# 06_LMS7002M_Power.net
KiCad netlist of a schematic drawn in Altium Designer
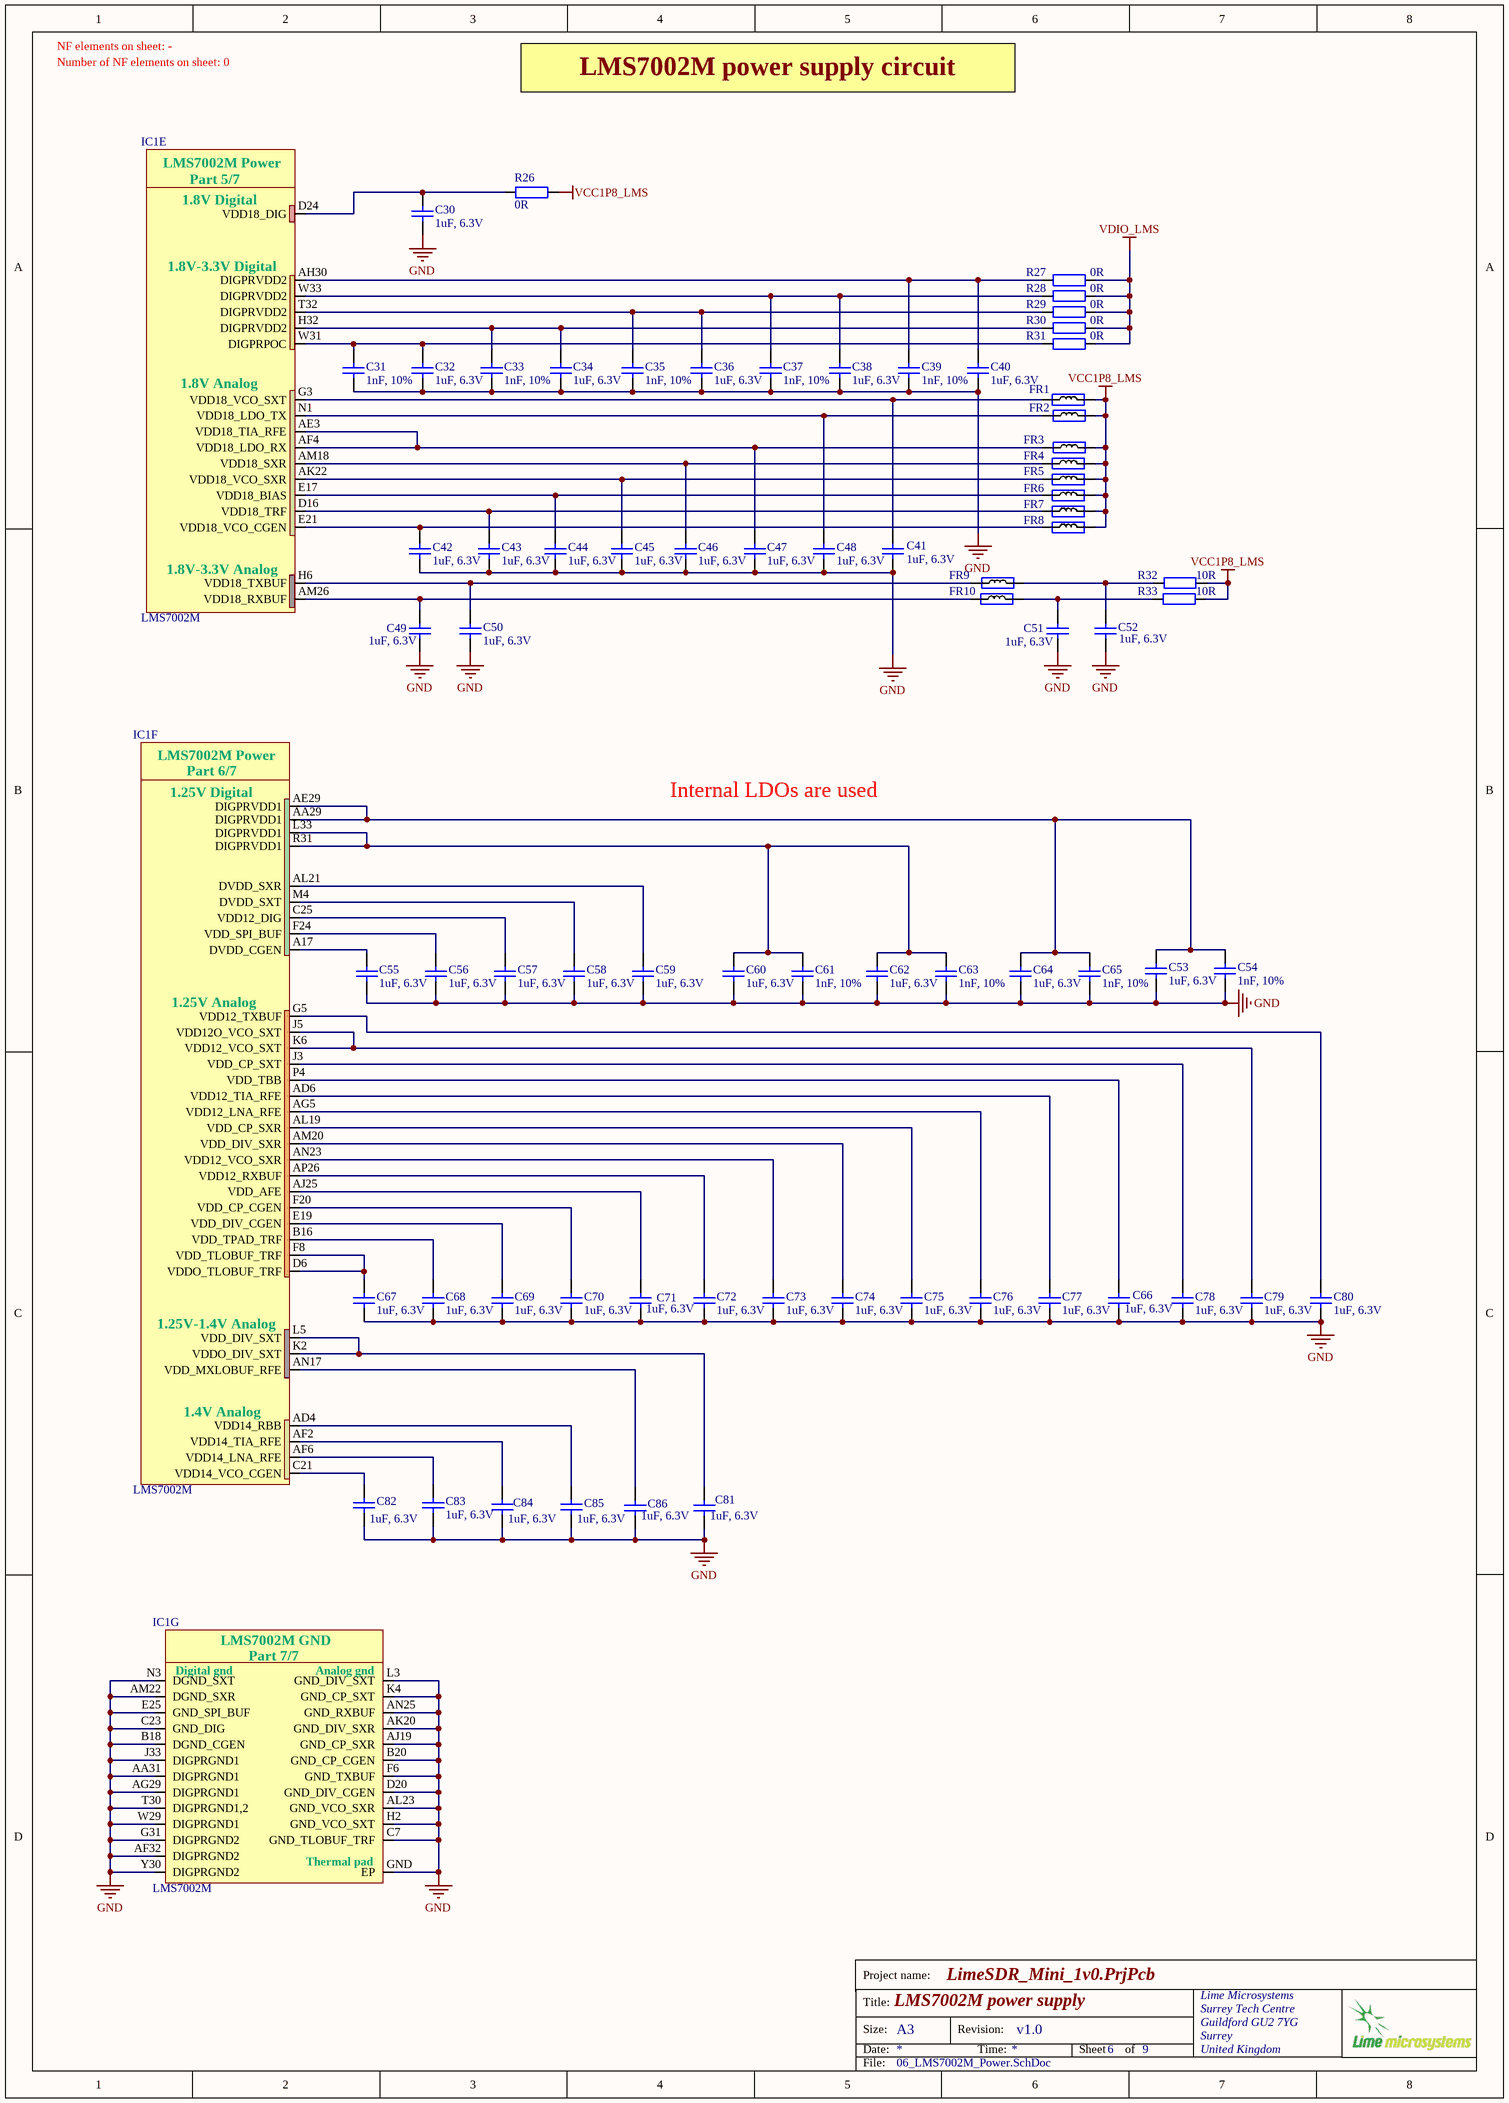
[diagram p0: 06_LMS7002M_Power.SchDoc]

(export (version "E")
  (design (tool "Eeschema 10.0.6"))
  (components
    (comp (ref "C30")
      (value "1uF, 6.3V")
      (footprint "CAP0201")
      (fields (field (name "TOLERANCE") "±20%") (field (name "MANUFACTURER") "TDK Corporation"))
      (libsource (lib "LimeMicroAltiumLib_schLib") (part "Cap_0402"))
    )
    (comp (ref "C31")
      (value "1nF, 10%")
      (footprint "CAP0201")
      (fields (field (name "TOLERANCE") "±10%") (field (name "MANUFACTURER") "TDK Corporation"))
      (libsource (lib "LimeMicroAltiumLib_schLib") (part "Cap_0402"))
    )
    (comp (ref "C32")
      (value "1uF, 6.3V")
      (footprint "CAP0201")
      (fields (field (name "TOLERANCE") "±20%") (field (name "MANUFACTURER") "TDK Corporation"))
      (libsource (lib "LimeMicroAltiumLib_schLib") (part "Cap_0402"))
    )
    (comp (ref "C33")
      (value "1nF, 10%")
      (footprint "CAP0201")
      (fields (field (name "TOLERANCE") "±10%") (field (name "MANUFACTURER") "TDK Corporation"))
      (libsource (lib "LimeMicroAltiumLib_schLib") (part "Cap_0402"))
    )
    (comp (ref "C34")
      (value "1uF, 6.3V")
      (footprint "CAP0201")
      (fields (field (name "TOLERANCE") "±20%") (field (name "MANUFACTURER") "TDK Corporation"))
      (libsource (lib "LimeMicroAltiumLib_schLib") (part "Cap_0402"))
    )
    (comp (ref "C35")
      (value "1nF, 10%")
      (footprint "CAP0201")
      (fields (field (name "TOLERANCE") "±10%") (field (name "MANUFACTURER") "TDK Corporation"))
      (libsource (lib "LimeMicroAltiumLib_schLib") (part "Cap_0402"))
    )
    (comp (ref "C36")
      (value "1uF, 6.3V")
      (footprint "CAP0201")
      (fields (field (name "TOLERANCE") "±20%") (field (name "MANUFACTURER") "TDK Corporation"))
      (libsource (lib "LimeMicroAltiumLib_schLib") (part "Cap_0402"))
    )
    (comp (ref "C37")
      (value "1nF, 10%")
      (footprint "CAP0201")
      (fields (field (name "TOLERANCE") "±10%") (field (name "MANUFACTURER") "TDK Corporation"))
      (libsource (lib "LimeMicroAltiumLib_schLib") (part "Cap_0402"))
    )
    (comp (ref "C38")
      (value "1uF, 6.3V")
      (footprint "CAP0201")
      (fields (field (name "TOLERANCE") "±20%") (field (name "MANUFACTURER") "TDK Corporation"))
      (libsource (lib "LimeMicroAltiumLib_schLib") (part "Cap_0402"))
    )
    (comp (ref "C39")
      (value "1nF, 10%")
      (footprint "CAP0201")
      (fields (field (name "TOLERANCE") "±10%") (field (name "MANUFACTURER") "TDK Corporation"))
      (libsource (lib "LimeMicroAltiumLib_schLib") (part "Cap_0402"))
    )
    (comp (ref "C40")
      (value "1uF, 6.3V")
      (footprint "CAP0201")
      (fields (field (name "TOLERANCE") "±20%") (field (name "MANUFACTURER") "TDK Corporation"))
      (libsource (lib "LimeMicroAltiumLib_schLib") (part "Cap_0402"))
    )
    (comp (ref "C41")
      (value "1uF, 6.3V")
      (footprint "CAP0201")
      (fields (field (name "TOLERANCE") "±20%") (field (name "MANUFACTURER") "TDK Corporation"))
      (libsource (lib "LimeMicroAltiumLib_schLib") (part "Cap_0402"))
    )
    (comp (ref "C42")
      (value "1uF, 6.3V")
      (footprint "CAP0201")
      (fields (field (name "TOLERANCE") "±20%") (field (name "MANUFACTURER") "TDK Corporation"))
      (libsource (lib "LimeMicroAltiumLib_schLib") (part "Cap_0402"))
    )
    (comp (ref "C43")
      (value "1uF, 6.3V")
      (footprint "CAP0201")
      (fields (field (name "TOLERANCE") "±20%") (field (name "MANUFACTURER") "TDK Corporation"))
      (libsource (lib "LimeMicroAltiumLib_schLib") (part "Cap_0402"))
    )
    (comp (ref "C44")
      (value "1uF, 6.3V")
      (footprint "CAP0201")
      (fields (field (name "TOLERANCE") "±20%") (field (name "MANUFACTURER") "TDK Corporation"))
      (libsource (lib "LimeMicroAltiumLib_schLib") (part "Cap_0402"))
    )
    (comp (ref "C45")
      (value "1uF, 6.3V")
      (footprint "CAP0201")
      (fields (field (name "TOLERANCE") "±20%") (field (name "MANUFACTURER") "TDK Corporation"))
      (libsource (lib "LimeMicroAltiumLib_schLib") (part "Cap_0402"))
    )
    (comp (ref "C46")
      (value "1uF, 6.3V")
      (footprint "CAP0201")
      (fields (field (name "TOLERANCE") "±20%") (field (name "MANUFACTURER") "TDK Corporation"))
      (libsource (lib "LimeMicroAltiumLib_schLib") (part "Cap_0402"))
    )
    (comp (ref "C47")
      (value "1uF, 6.3V")
      (footprint "CAP0201")
      (fields (field (name "TOLERANCE") "±20%") (field (name "MANUFACTURER") "TDK Corporation"))
      (libsource (lib "LimeMicroAltiumLib_schLib") (part "Cap_0402"))
    )
    (comp (ref "C48")
      (value "1uF, 6.3V")
      (footprint "CAP0201")
      (fields (field (name "TOLERANCE") "±20%") (field (name "MANUFACTURER") "TDK Corporation"))
      (libsource (lib "LimeMicroAltiumLib_schLib") (part "Cap_0402"))
    )
    (comp (ref "C49")
      (value "1uF, 6.3V")
      (footprint "CAP0201")
      (fields (field (name "TOLERANCE") "±20%") (field (name "MANUFACTURER") "TDK Corporation"))
      (libsource (lib "LimeMicroAltiumLib_schLib") (part "Cap_0402"))
    )
    (comp (ref "C50")
      (value "1uF, 6.3V")
      (footprint "CAP0201")
      (fields (field (name "TOLERANCE") "±20%") (field (name "MANUFACTURER") "TDK Corporation"))
      (libsource (lib "LimeMicroAltiumLib_schLib") (part "Cap_0402"))
    )
    (comp (ref "C51")
      (value "1uF, 6.3V")
      (footprint "CAP0201")
      (fields (field (name "TOLERANCE") "±20%") (field (name "MANUFACTURER") "TDK Corporation"))
      (libsource (lib "LimeMicroAltiumLib_schLib") (part "Cap_0402"))
    )
    (comp (ref "C52")
      (value "1uF, 6.3V")
      (footprint "CAP0201")
      (fields (field (name "TOLERANCE") "±20%") (field (name "MANUFACTURER") "TDK Corporation"))
      (libsource (lib "LimeMicroAltiumLib_schLib") (part "Cap_0402"))
    )
    (comp (ref "C53")
      (value "1uF, 6.3V")
      (footprint "CAP0201")
      (fields (field (name "TOLERANCE") "±20%") (field (name "MANUFACTURER") "TDK Corporation"))
      (libsource (lib "LimeMicroAltiumLib_schLib") (part "Cap_0402"))
    )
    (comp (ref "C54")
      (value "1nF, 10%")
      (footprint "CAP0201")
      (fields (field (name "TOLERANCE") "±10%") (field (name "MANUFACTURER") "TDK Corporation"))
      (libsource (lib "LimeMicroAltiumLib_schLib") (part "Cap_0402"))
    )
    (comp (ref "C55")
      (value "1uF, 6.3V")
      (footprint "CAP0201")
      (fields (field (name "TOLERANCE") "±20%") (field (name "MANUFACTURER") "TDK Corporation"))
      (libsource (lib "LimeMicroAltiumLib_schLib") (part "Cap_0402"))
    )
    (comp (ref "C56")
      (value "1uF, 6.3V")
      (footprint "CAP0201")
      (fields (field (name "TOLERANCE") "±20%") (field (name "MANUFACTURER") "TDK Corporation"))
      (libsource (lib "LimeMicroAltiumLib_schLib") (part "Cap_0402"))
    )
    (comp (ref "C57")
      (value "1uF, 6.3V")
      (footprint "CAP0201")
      (fields (field (name "TOLERANCE") "±20%") (field (name "MANUFACTURER") "TDK Corporation"))
      (libsource (lib "LimeMicroAltiumLib_schLib") (part "Cap_0402"))
    )
    (comp (ref "C58")
      (value "1uF, 6.3V")
      (footprint "CAP0201")
      (fields (field (name "TOLERANCE") "±20%") (field (name "MANUFACTURER") "TDK Corporation"))
      (libsource (lib "LimeMicroAltiumLib_schLib") (part "Cap_0402"))
    )
    (comp (ref "C59")
      (value "1uF, 6.3V")
      (footprint "CAP0201")
      (fields (field (name "TOLERANCE") "±20%") (field (name "MANUFACTURER") "TDK Corporation"))
      (libsource (lib "LimeMicroAltiumLib_schLib") (part "Cap_0402"))
    )
    (comp (ref "C60")
      (value "1uF, 6.3V")
      (footprint "CAP0201")
      (fields (field (name "TOLERANCE") "±20%") (field (name "MANUFACTURER") "TDK Corporation"))
      (libsource (lib "LimeMicroAltiumLib_schLib") (part "Cap_0402"))
    )
    (comp (ref "C61")
      (value "1nF, 10%")
      (footprint "CAP0201")
      (fields (field (name "TOLERANCE") "±10%") (field (name "MANUFACTURER") "TDK Corporation"))
      (libsource (lib "LimeMicroAltiumLib_schLib") (part "Cap_0402"))
    )
    (comp (ref "C62")
      (value "1uF, 6.3V")
      (footprint "CAP0201")
      (fields (field (name "TOLERANCE") "±20%") (field (name "MANUFACTURER") "TDK Corporation"))
      (libsource (lib "LimeMicroAltiumLib_schLib") (part "Cap_0402"))
    )
    (comp (ref "C63")
      (value "1nF, 10%")
      (footprint "CAP0201")
      (fields (field (name "TOLERANCE") "±10%") (field (name "MANUFACTURER") "TDK Corporation"))
      (libsource (lib "LimeMicroAltiumLib_schLib") (part "Cap_0402"))
    )
    (comp (ref "C64")
      (value "1uF, 6.3V")
      (footprint "CAP0201")
      (fields (field (name "TOLERANCE") "±20%") (field (name "MANUFACTURER") "TDK Corporation"))
      (libsource (lib "LimeMicroAltiumLib_schLib") (part "Cap_0402"))
    )
    (comp (ref "C65")
      (value "1nF, 10%")
      (footprint "CAP0201")
      (fields (field (name "TOLERANCE") "±10%") (field (name "MANUFACTURER") "TDK Corporation"))
      (libsource (lib "LimeMicroAltiumLib_schLib") (part "Cap_0402"))
    )
    (comp (ref "C66")
      (value "1uF, 6.3V")
      (footprint "CAP0201")
      (fields (field (name "TOLERANCE") "±20%") (field (name "MANUFACTURER") "TDK Corporation"))
      (libsource (lib "LimeMicroAltiumLib_schLib") (part "Cap_0402"))
    )
    (comp (ref "C67")
      (value "1uF, 6.3V")
      (footprint "CAP0201")
      (fields (field (name "TOLERANCE") "±20%") (field (name "MANUFACTURER") "TDK Corporation"))
      (libsource (lib "LimeMicroAltiumLib_schLib") (part "Cap_0402"))
    )
    (comp (ref "C68")
      (value "1uF, 6.3V")
      (footprint "CAP0201")
      (fields (field (name "TOLERANCE") "±20%") (field (name "MANUFACTURER") "TDK Corporation"))
      (libsource (lib "LimeMicroAltiumLib_schLib") (part "Cap_0402"))
    )
    (comp (ref "C69")
      (value "1uF, 6.3V")
      (footprint "CAP0201")
      (fields (field (name "TOLERANCE") "±20%") (field (name "MANUFACTURER") "TDK Corporation"))
      (libsource (lib "LimeMicroAltiumLib_schLib") (part "Cap_0402"))
    )
    (comp (ref "C70")
      (value "1uF, 6.3V")
      (footprint "CAP0201")
      (fields (field (name "TOLERANCE") "±20%") (field (name "MANUFACTURER") "TDK Corporation"))
      (libsource (lib "LimeMicroAltiumLib_schLib") (part "Cap_0402"))
    )
    (comp (ref "C71")
      (value "1uF, 6.3V")
      (footprint "CAP0201")
      (fields (field (name "TOLERANCE") "±20%") (field (name "MANUFACTURER") "TDK Corporation"))
      (libsource (lib "LimeMicroAltiumLib_schLib") (part "Cap_0402"))
    )
    (comp (ref "C72")
      (value "1uF, 6.3V")
      (footprint "CAP0201")
      (fields (field (name "TOLERANCE") "±20%") (field (name "MANUFACTURER") "TDK Corporation"))
      (libsource (lib "LimeMicroAltiumLib_schLib") (part "Cap_0402"))
    )
    (comp (ref "C73")
      (value "1uF, 6.3V")
      (footprint "CAP0201")
      (fields (field (name "TOLERANCE") "±20%") (field (name "MANUFACTURER") "TDK Corporation"))
      (libsource (lib "LimeMicroAltiumLib_schLib") (part "Cap_0402"))
    )
    (comp (ref "C74")
      (value "1uF, 6.3V")
      (footprint "CAP0201")
      (fields (field (name "TOLERANCE") "±20%") (field (name "MANUFACTURER") "TDK Corporation"))
      (libsource (lib "LimeMicroAltiumLib_schLib") (part "Cap_0402"))
    )
    (comp (ref "C75")
      (value "1uF, 6.3V")
      (footprint "CAP0201")
      (fields (field (name "TOLERANCE") "±20%") (field (name "MANUFACTURER") "TDK Corporation"))
      (libsource (lib "LimeMicroAltiumLib_schLib") (part "Cap_0402"))
    )
    (comp (ref "C76")
      (value "1uF, 6.3V")
      (footprint "CAP0201")
      (fields (field (name "TOLERANCE") "±20%") (field (name "MANUFACTURER") "TDK Corporation"))
      (libsource (lib "LimeMicroAltiumLib_schLib") (part "Cap_0402"))
    )
    (comp (ref "C77")
      (value "1uF, 6.3V")
      (footprint "CAP0201")
      (fields (field (name "TOLERANCE") "±20%") (field (name "MANUFACTURER") "TDK Corporation"))
      (libsource (lib "LimeMicroAltiumLib_schLib") (part "Cap_0402"))
    )
    (comp (ref "C78")
      (value "1uF, 6.3V")
      (footprint "CAP0201")
      (fields (field (name "TOLERANCE") "±20%") (field (name "MANUFACTURER") "TDK Corporation"))
      (libsource (lib "LimeMicroAltiumLib_schLib") (part "Cap_0402"))
    )
    (comp (ref "C79")
      (value "1uF, 6.3V")
      (footprint "CAP0201")
      (fields (field (name "TOLERANCE") "±20%") (field (name "MANUFACTURER") "TDK Corporation"))
      (libsource (lib "LimeMicroAltiumLib_schLib") (part "Cap_0402"))
    )
    (comp (ref "C80")
      (value "1uF, 6.3V")
      (footprint "CAP0201")
      (fields (field (name "TOLERANCE") "±20%") (field (name "MANUFACTURER") "TDK Corporation"))
      (libsource (lib "LimeMicroAltiumLib_schLib") (part "Cap_0402"))
    )
    (comp (ref "C81")
      (value "1uF, 6.3V")
      (footprint "CAP0201")
      (fields (field (name "TOLERANCE") "±20%") (field (name "MANUFACTURER") "TDK Corporation"))
      (libsource (lib "LimeMicroAltiumLib_schLib") (part "Cap_0402"))
    )
    (comp (ref "C82")
      (value "1uF, 6.3V")
      (footprint "CAP0201")
      (fields (field (name "TOLERANCE") "±20%") (field (name "MANUFACTURER") "TDK Corporation"))
      (libsource (lib "LimeMicroAltiumLib_schLib") (part "Cap_0402"))
    )
    (comp (ref "C83")
      (value "1uF, 6.3V")
      (footprint "CAP0201")
      (fields (field (name "TOLERANCE") "±20%") (field (name "MANUFACTURER") "TDK Corporation"))
      (libsource (lib "LimeMicroAltiumLib_schLib") (part "Cap_0402"))
    )
    (comp (ref "C84")
      (value "1uF, 6.3V")
      (footprint "CAP0201")
      (fields (field (name "TOLERANCE") "±20%") (field (name "MANUFACTURER") "TDK Corporation"))
      (libsource (lib "LimeMicroAltiumLib_schLib") (part "Cap_0402"))
    )
    (comp (ref "C85")
      (value "1uF, 6.3V")
      (footprint "CAP0201")
      (fields (field (name "TOLERANCE") "±20%") (field (name "MANUFACTURER") "TDK Corporation"))
      (libsource (lib "LimeMicroAltiumLib_schLib") (part "Cap_0402"))
    )
    (comp (ref "C86")
      (value "1uF, 6.3V")
      (footprint "CAP0201")
      (fields (field (name "TOLERANCE") "±20%") (field (name "MANUFACTURER") "TDK Corporation"))
      (libsource (lib "LimeMicroAltiumLib_schLib") (part "Cap_0402"))
    )
    (comp (ref "FR1")
      (value "600R, 0.27A")
      (footprint "RES0201")
      (fields (field (name "MANUFACTURER") "Taiyo Yuden"))
      (libsource (lib "") (part "Ferrite_1"))
    )
    (comp (ref "FR2")
      (value "600R, 0.27A")
      (footprint "RES0201")
      (fields (field (name "MANUFACTURER") "Taiyo Yuden"))
      (libsource (lib "LimeMicroAltiumLib_schLib") (part "Ferrite"))
    )
    (comp (ref "FR3")
      (value "600R, 0.27A")
      (footprint "RES0201")
      (fields (field (name "MANUFACTURER") "Taiyo Yuden"))
      (libsource (lib "LimeMicroAltiumLib_schLib") (part "Ferrite"))
    )
    (comp (ref "FR4")
      (value "600R, 0.27A")
      (footprint "RES0201")
      (fields (field (name "MANUFACTURER") "Taiyo Yuden"))
      (libsource (lib "") (part "Ferrite_1"))
    )
    (comp (ref "FR5")
      (value "600R, 0.27A")
      (footprint "RES0201")
      (fields (field (name "MANUFACTURER") "Taiyo Yuden"))
      (libsource (lib "") (part "Ferrite_1"))
    )
    (comp (ref "FR6")
      (value "600R, 0.27A")
      (footprint "RES0201")
      (fields (field (name "MANUFACTURER") "Taiyo Yuden"))
      (libsource (lib "") (part "Ferrite_1"))
    )
    (comp (ref "FR7")
      (value "600R, 0.27A")
      (footprint "RES0201")
      (fields (field (name "MANUFACTURER") "Taiyo Yuden"))
      (libsource (lib "") (part "Ferrite_1"))
    )
    (comp (ref "FR8")
      (value "600R, 0.27A")
      (footprint "RES0201")
      (fields (field (name "MANUFACTURER") "Taiyo Yuden"))
      (libsource (lib "") (part "Ferrite_1"))
    )
    (comp (ref "FR9")
      (value "600R, 0.27A")
      (footprint "RES0201")
      (fields (field (name "MANUFACTURER") "Taiyo Yuden"))
      (libsource (lib "LimeMicroAltiumLib_schLib") (part "Ferrite"))
    )
    (comp (ref "FR10")
      (value "600R, 0.27A")
      (footprint "RES0201")
      (fields (field (name "MANUFACTURER") "Taiyo Yuden"))
      (libsource (lib "") (part "Ferrite_1"))
    )
    (comp (ref "IC1")
      (value "LMS7002M")
      (footprint "LMS7002M_v4")
      (description "Schematic symbol revision 3. Default footprint - 0.31mm pad")
      (fields (field (name "MANUFACTURER") "Lime Microsystems"))
      (libsource (lib "LimeMicroAltiumLib_schLib") (part "LMS7002Mr3"))
    )
    (comp (ref "R26")
      (value "0R")
      (footprint "RES0201")
      (fields (field (name "MANUFACTURER") "Rohm Semiconductor") (field (name "TOLERANCE") "Jumper"))
      (libsource (lib "LimeMicroAltiumLib_schLib") (part "Res_0402"))
    )
    (comp (ref "R27")
      (value "0R")
      (footprint "RES0402")
      (fields (field (name "MANUFACTURER") "Yageo") (field (name "TOLERANCE") "Jumper"))
      (libsource (lib "LimeMicroAltiumLib_schLib") (part "Res_0402"))
    )
    (comp (ref "R28")
      (value "0R")
      (footprint "RES0402")
      (fields (field (name "MANUFACTURER") "Yageo") (field (name "TOLERANCE") "Jumper"))
      (libsource (lib "LimeMicroAltiumLib_schLib") (part "Res_0402"))
    )
    (comp (ref "R29")
      (value "0R")
      (footprint "RES0402")
      (fields (field (name "MANUFACTURER") "Yageo") (field (name "TOLERANCE") "Jumper"))
      (libsource (lib "LimeMicroAltiumLib_schLib") (part "Res_0402"))
    )
    (comp (ref "R30")
      (value "0R")
      (footprint "RES0402")
      (fields (field (name "MANUFACTURER") "Yageo") (field (name "TOLERANCE") "Jumper"))
      (libsource (lib "LimeMicroAltiumLib_schLib") (part "Res_0402"))
    )
    (comp (ref "R31")
      (value "0R")
      (footprint "RES0402")
      (fields (field (name "MANUFACTURER") "Yageo") (field (name "TOLERANCE") "Jumper"))
      (libsource (lib "LimeMicroAltiumLib_schLib") (part "Res_0402"))
    )
    (comp (ref "R32")
      (value "10R")
      (footprint "RES0201")
      (fields
        (field (name "MANUFACTURER") "Panasonic Electronic Components")
        (field (name "TOLERANCE") "±1%")
        (field (name "MANUFACTURER PART NUMBER") "ERJ-1GEF10R0C")
      )
      (libsource (lib "LimeMicroAltiumLib_schLib") (part "Res_0402"))
    )
    (comp (ref "R33")
      (value "10R")
      (footprint "RES0201")
      (fields
        (field (name "MANUFACTURER") "Panasonic Electronic Components")
        (field (name "TOLERANCE") "±1%")
        (field (name "MANUFACTURER PART NUMBER") "ERJ-1GEF10R0C")
      )
      (libsource (lib "LimeMicroAltiumLib_schLib") (part "Res_0402"))
    )
  )
  (nets
    (net (code "1") (name "GND") (class "Default")
      (node (ref "C30") (pin "2") (pinfunction "2_2") (pintype "passive"))
      (node (ref "C31") (pin "2") (pinfunction "2_2") (pintype "passive"))
      (node (ref "C32") (pin "2") (pinfunction "2_2") (pintype "passive"))
      (node (ref "C33") (pin "2") (pinfunction "2_2") (pintype "passive"))
      (node (ref "C34") (pin "2") (pinfunction "2_2") (pintype "passive"))
      (node (ref "C35") (pin "2") (pinfunction "2_2") (pintype "passive"))
      (node (ref "C36") (pin "2") (pinfunction "2_2") (pintype "passive"))
      (node (ref "C37") (pin "2") (pinfunction "2_2") (pintype "passive"))
      (node (ref "C38") (pin "2") (pinfunction "2_2") (pintype "passive"))
      (node (ref "C39") (pin "2") (pinfunction "2_2") (pintype "passive"))
      (node (ref "C40") (pin "2") (pinfunction "2_2") (pintype "passive"))
      (node (ref "C41") (pin "2") (pinfunction "2_2") (pintype "passive"))
      (node (ref "C42") (pin "2") (pinfunction "2_2") (pintype "passive"))
      (node (ref "C43") (pin "2") (pinfunction "2_2") (pintype "passive"))
      (node (ref "C44") (pin "2") (pinfunction "2_2") (pintype "passive"))
      (node (ref "C45") (pin "2") (pinfunction "2_2") (pintype "passive"))
      (node (ref "C46") (pin "2") (pinfunction "2_2") (pintype "passive"))
      (node (ref "C47") (pin "2") (pinfunction "2_2") (pintype "passive"))
      (node (ref "C48") (pin "2") (pinfunction "2_2") (pintype "passive"))
      (node (ref "C49") (pin "2") (pinfunction "2_2") (pintype "passive"))
      (node (ref "C50") (pin "2") (pinfunction "2_2") (pintype "passive"))
      (node (ref "C51") (pin "2") (pinfunction "2_2") (pintype "passive"))
      (node (ref "C52") (pin "2") (pinfunction "2_2") (pintype "passive"))
      (node (ref "C53") (pin "2") (pinfunction "2_2") (pintype "passive"))
      (node (ref "C54") (pin "2") (pinfunction "2_2") (pintype "passive"))
      (node (ref "C55") (pin "2") (pinfunction "2_2") (pintype "passive"))
      (node (ref "C56") (pin "2") (pinfunction "2_2") (pintype "passive"))
      (node (ref "C57") (pin "2") (pinfunction "2_2") (pintype "passive"))
      (node (ref "C58") (pin "1") (pinfunction "1_1") (pintype "passive"))
      (node (ref "C59") (pin "2") (pinfunction "2_2") (pintype "passive"))
      (node (ref "C60") (pin "2") (pinfunction "2_2") (pintype "passive"))
      (node (ref "C61") (pin "2") (pinfunction "2_2") (pintype "passive"))
      (node (ref "C62") (pin "2") (pinfunction "2_2") (pintype "passive"))
      (node (ref "C63") (pin "2") (pinfunction "2_2") (pintype "passive"))
      (node (ref "C64") (pin "2") (pinfunction "2_2") (pintype "passive"))
      (node (ref "C65") (pin "2") (pinfunction "2_2") (pintype "passive"))
      (node (ref "C66") (pin "2") (pinfunction "2_2") (pintype "passive"))
      (node (ref "C67") (pin "2") (pinfunction "2_2") (pintype "passive"))
      (node (ref "C68") (pin "2") (pinfunction "2_2") (pintype "passive"))
      (node (ref "C69") (pin "2") (pinfunction "2_2") (pintype "passive"))
      (node (ref "C70") (pin "1") (pinfunction "1_1") (pintype "passive"))
      (node (ref "C71") (pin "2") (pinfunction "2_2") (pintype "passive"))
      (node (ref "C72") (pin "2") (pinfunction "2_2") (pintype "passive"))
      (node (ref "C73") (pin "2") (pinfunction "2_2") (pintype "passive"))
      (node (ref "C74") (pin "2") (pinfunction "2_2") (pintype "passive"))
      (node (ref "C75") (pin "2") (pinfunction "2_2") (pintype "passive"))
      (node (ref "C76") (pin "2") (pinfunction "2_2") (pintype "passive"))
      (node (ref "C77") (pin "1") (pinfunction "1_1") (pintype "passive"))
      (node (ref "C78") (pin "2") (pinfunction "2_2") (pintype "passive"))
      (node (ref "C79") (pin "1") (pinfunction "1_1") (pintype "passive"))
      (node (ref "C80") (pin "2") (pinfunction "2_2") (pintype "passive"))
      (node (ref "C81") (pin "2") (pinfunction "2_2") (pintype "passive"))
      (node (ref "C82") (pin "2") (pinfunction "2_2") (pintype "passive"))
      (node (ref "C83") (pin "2") (pinfunction "2_2") (pintype "passive"))
      (node (ref "C84") (pin "2") (pinfunction "2_2") (pintype "passive"))
      (node (ref "C85") (pin "2") (pinfunction "2_2") (pintype "passive"))
      (node (ref "C86") (pin "2") (pinfunction "2_2") (pintype "passive"))
      (node (ref "IC1") (pin "AA31") (pinfunction "DIGPRGND1_AA31") (pintype "passive"))
      (node (ref "IC1") (pin "AF32") (pinfunction "DIGPRGND2_AF32") (pintype "passive"))
      (node (ref "IC1") (pin "AG29") (pinfunction "DIGPRGND1_AG29") (pintype "passive"))
      (node (ref "IC1") (pin "AJ19") (pinfunction "GND_CP_SXR_AJ19") (pintype "passive"))
      (node (ref "IC1") (pin "AK20") (pinfunction "GND_DIV_SXR_AK20") (pintype "passive"))
      (node (ref "IC1") (pin "AL23") (pinfunction "GND_VCO_SXR_AL23") (pintype "passive"))
      (node (ref "IC1") (pin "AM22") (pinfunction "DGND_SXR_AM22") (pintype "passive"))
      (node (ref "IC1") (pin "AN25") (pinfunction "GND_RXBUF_AN25") (pintype "passive"))
      (node (ref "IC1") (pin "B18") (pinfunction "DGND_CGEN_B18") (pintype "passive"))
      (node (ref "IC1") (pin "B20") (pinfunction "GND_CP_CGEN_B20") (pintype "passive"))
      (node (ref "IC1") (pin "C23") (pinfunction "GND_DIG_C23") (pintype "passive"))
      (node (ref "IC1") (pin "C7") (pinfunction "GND_TLOBUF_TRF_C7") (pintype "passive"))
      (node (ref "IC1") (pin "D20") (pinfunction "GND_DIV_CGEN_D20") (pintype "passive"))
      (node (ref "IC1") (pin "E25") (pinfunction "GND_SPI_BUF_E25") (pintype "passive"))
      (node (ref "IC1") (pin "F6") (pinfunction "GND_TXBUF_F6") (pintype "passive"))
      (node (ref "IC1") (pin "G31") (pinfunction "DIGPRGND2_G31") (pintype "passive"))
      (node (ref "IC1") (pin "GND") (pinfunction "EP_GND") (pintype "passive"))
      (node (ref "IC1") (pin "H2") (pinfunction "GND_VCO_SXT_H2") (pintype "passive"))
      (node (ref "IC1") (pin "J33") (pinfunction "DIGPRGND1_J33") (pintype "passive"))
      (node (ref "IC1") (pin "K4") (pinfunction "GND_CP_SXT_K4") (pintype "passive"))
      (node (ref "IC1") (pin "L3") (pinfunction "GND_DIV_SXT_L3") (pintype "passive"))
      (node (ref "IC1") (pin "N3") (pinfunction "DGND_SXT_N3") (pintype "passive"))
      (node (ref "IC1") (pin "T30") (pinfunction "DIGPRGND1,2_T30") (pintype "passive"))
      (node (ref "IC1") (pin "W29") (pinfunction "DIGPRGND1_W29") (pintype "passive"))
      (node (ref "IC1") (pin "Y30") (pinfunction "DIGPRGND2_Y30") (pintype "passive"))
    )
    (net (code "2") (name "Net-(C33-Pad1)") (class "Default")
      (node (ref "C33") (pin "1") (pinfunction "1_1") (pintype "passive"))
      (node (ref "C34") (pin "1") (pinfunction "1_1") (pintype "passive"))
      (node (ref "IC1") (pin "H32") (pinfunction "DIGPRVDD2_H32") (pintype "power_in"))
      (node (ref "R30") (pin "2") (pinfunction "2_2") (pintype "passive"))
    )
    (net (code "3") (name "Net-(C35-Pad1)") (class "Default")
      (node (ref "C35") (pin "1") (pinfunction "1_1") (pintype "passive"))
      (node (ref "C36") (pin "1") (pinfunction "1_1") (pintype "passive"))
      (node (ref "IC1") (pin "T32") (pinfunction "DIGPRVDD2_T32") (pintype "power_in"))
      (node (ref "R29") (pin "2") (pinfunction "2_2") (pintype "passive"))
    )
    (net (code "4") (name "Net-(C37-Pad1)") (class "Default")
      (node (ref "C37") (pin "1") (pinfunction "1_1") (pintype "passive"))
      (node (ref "C38") (pin "1") (pinfunction "1_1") (pintype "passive"))
      (node (ref "IC1") (pin "W33") (pinfunction "DIGPRVDD2_W33") (pintype "power_in"))
      (node (ref "R28") (pin "2") (pinfunction "2_2") (pintype "passive"))
    )
    (net (code "5") (name "Net-(C39-Pad1)") (class "Default")
      (node (ref "C39") (pin "1") (pinfunction "1_1") (pintype "passive"))
      (node (ref "C40") (pin "1") (pinfunction "1_1") (pintype "passive"))
      (node (ref "IC1") (pin "AH30") (pinfunction "DIGPRVDD2_AH30") (pintype "power_in"))
      (node (ref "R27") (pin "2") (pinfunction "2_2") (pintype "passive"))
    )
    (net (code "6") (name "Net-(C51-Pad1)") (class "Default")
      (node (ref "C51") (pin "1") (pinfunction "1_1") (pintype "passive"))
      (node (ref "FR10") (pin "2") (pinfunction "2_2") (pintype "passive"))
      (node (ref "R33") (pin "2") (pinfunction "2_2") (pintype "passive"))
    )
    (net (code "7") (name "Net-(C52-Pad1)") (class "Default")
      (node (ref "C52") (pin "1") (pinfunction "1_1") (pintype "passive"))
      (node (ref "FR9") (pin "1") (pinfunction "1_1") (pintype "passive"))
      (node (ref "R32") (pin "1") (pinfunction "1_1") (pintype "passive"))
    )
    (net (code "8") (name "Net-(C53-Pad1)") (class "Default")
      (node (ref "C53") (pin "1") (pinfunction "1_1") (pintype "passive"))
      (node (ref "C54") (pin "1") (pinfunction "1_1") (pintype "passive"))
      (node (ref "C64") (pin "1") (pinfunction "1_1") (pintype "passive"))
      (node (ref "C65") (pin "1") (pinfunction "1_1") (pintype "passive"))
      (node (ref "IC1") (pin "AA29") (pinfunction "DIGPRVDD1_AA29") (pintype "power_in"))
      (node (ref "IC1") (pin "AE29") (pinfunction "DIGPRVDD1_AE29") (pintype "power_in"))
    )
    (net (code "9") (name "Net-(C60-Pad1)") (class "Default")
      (node (ref "C60") (pin "1") (pinfunction "1_1") (pintype "passive"))
      (node (ref "C61") (pin "1") (pinfunction "1_1") (pintype "passive"))
      (node (ref "C62") (pin "1") (pinfunction "1_1") (pintype "passive"))
      (node (ref "C63") (pin "1") (pinfunction "1_1") (pintype "passive"))
      (node (ref "IC1") (pin "L33") (pinfunction "DIGPRVDD1_L33") (pintype "power_in"))
      (node (ref "IC1") (pin "R31") (pinfunction "DIGPRVDD1_R31") (pintype "power_in"))
    )
    (net (code "10") (name "Net-(IC1E-DIGPRPOC)") (class "Default")
      (node (ref "C31") (pin "1") (pinfunction "1_1") (pintype "passive"))
      (node (ref "C32") (pin "1") (pinfunction "1_1") (pintype "passive"))
      (node (ref "IC1") (pin "W31") (pinfunction "DIGPRPOC_W31") (pintype "power_in"))
      (node (ref "R31") (pin "2") (pinfunction "2_2") (pintype "passive"))
    )
    (net (code "11") (name "Net-(IC1E-VDD18_BIAS)") (class "Default")
      (node (ref "C44") (pin "1") (pinfunction "1_1") (pintype "passive"))
      (node (ref "FR6") (pin "1") (pinfunction "1_1") (pintype "passive"))
      (node (ref "IC1") (pin "E17") (pinfunction "VDD18_BIAS_E17") (pintype "power_in"))
    )
    (net (code "12") (name "Net-(IC1E-VDD18_DIG)") (class "Default")
      (node (ref "C30") (pin "1") (pinfunction "1_1") (pintype "passive"))
      (node (ref "IC1") (pin "D24") (pinfunction "VDD18_DIG_D24") (pintype "power_in"))
      (node (ref "R26") (pin "1") (pinfunction "1_1") (pintype "passive"))
    )
    (net (code "13") (name "Net-(IC1E-VDD18_LDO_RX)") (class "Default")
      (node (ref "C47") (pin "1") (pinfunction "1_1") (pintype "passive"))
      (node (ref "FR3") (pin "2") (pinfunction "2_2") (pintype "passive"))
      (node (ref "IC1") (pin "AE3") (pinfunction "VDD18_TIA_RFE_AE3") (pintype "power_in"))
      (node (ref "IC1") (pin "AF4") (pinfunction "VDD18_LDO_RX_AF4") (pintype "power_in"))
    )
    (net (code "14") (name "Net-(IC1E-VDD18_LDO_TX)") (class "Default")
      (node (ref "C48") (pin "1") (pinfunction "1_1") (pintype "passive"))
      (node (ref "FR2") (pin "2") (pinfunction "2_2") (pintype "passive"))
      (node (ref "IC1") (pin "N1") (pinfunction "VDD18_LDO_TX_N1") (pintype "power_in"))
    )
    (net (code "15") (name "Net-(IC1E-VDD18_RXBUF)") (class "Default")
      (node (ref "C49") (pin "1") (pinfunction "1_1") (pintype "passive"))
      (node (ref "FR10") (pin "1") (pinfunction "1_1") (pintype "passive"))
      (node (ref "IC1") (pin "AM26") (pinfunction "VDD18_RXBUF_AM26") (pintype "power_in"))
    )
    (net (code "16") (name "Net-(IC1E-VDD18_SXR)") (class "Default")
      (node (ref "C46") (pin "1") (pinfunction "1_1") (pintype "passive"))
      (node (ref "FR4") (pin "1") (pinfunction "1_1") (pintype "passive"))
      (node (ref "IC1") (pin "AM18") (pinfunction "VDD18_SXR_AM18") (pintype "power_in"))
    )
    (net (code "17") (name "Net-(IC1E-VDD18_TRF)") (class "Default")
      (node (ref "C43") (pin "1") (pinfunction "1_1") (pintype "passive"))
      (node (ref "FR7") (pin "1") (pinfunction "1_1") (pintype "passive"))
      (node (ref "IC1") (pin "D16") (pinfunction "VDD18_TRF_D16") (pintype "power_in"))
    )
    (net (code "18") (name "Net-(IC1E-VDD18_TXBUF)") (class "Default")
      (node (ref "C50") (pin "1") (pinfunction "1_1") (pintype "passive"))
      (node (ref "FR9") (pin "2") (pinfunction "2_2") (pintype "passive"))
      (node (ref "IC1") (pin "H6") (pinfunction "VDD18_TXBUF_H6") (pintype "power_in"))
    )
    (net (code "19") (name "Net-(IC1E-VDD18_VCO_CGEN)") (class "Default")
      (node (ref "C42") (pin "1") (pinfunction "1_1") (pintype "passive"))
      (node (ref "FR8") (pin "1") (pinfunction "1_1") (pintype "passive"))
      (node (ref "IC1") (pin "E21") (pinfunction "VDD18_VCO_CGEN_E21") (pintype "power_in"))
    )
    (net (code "20") (name "Net-(IC1E-VDD18_VCO_SXR)") (class "Default")
      (node (ref "C45") (pin "1") (pinfunction "1_1") (pintype "passive"))
      (node (ref "FR5") (pin "1") (pinfunction "1_1") (pintype "passive"))
      (node (ref "IC1") (pin "AK22") (pinfunction "VDD18_VCO_SXR_AK22") (pintype "power_in"))
    )
    (net (code "21") (name "Net-(IC1E-VDD18_VCO_SXT)") (class "Default")
      (node (ref "C41") (pin "1") (pinfunction "1_1") (pintype "passive"))
      (node (ref "FR1") (pin "1") (pinfunction "1_1") (pintype "passive"))
      (node (ref "IC1") (pin "G3") (pinfunction "VDD18_VCO_SXT_G3") (pintype "power_in"))
    )
    (net (code "22") (name "Net-(IC1F-DVDD_CGEN)") (class "Default")
      (node (ref "C55") (pin "1") (pinfunction "1_1") (pintype "passive"))
      (node (ref "IC1") (pin "A17") (pinfunction "DVDD_CGEN_A17") (pintype "power_in"))
    )
    (net (code "23") (name "Net-(IC1F-DVDD_SXR)") (class "Default")
      (node (ref "C59") (pin "1") (pinfunction "1_1") (pintype "passive"))
      (node (ref "IC1") (pin "AL21") (pinfunction "DVDD_SXR_AL21") (pintype "power_in"))
    )
    (net (code "24") (name "Net-(IC1F-DVDD_SXT)") (class "Default")
      (node (ref "C58") (pin "2") (pinfunction "2_2") (pintype "passive"))
      (node (ref "IC1") (pin "M4") (pinfunction "DVDD_SXT_M4") (pintype "power_in"))
    )
    (net (code "25") (name "Net-(IC1F-VDD12O_VCO_SXT)") (class "Default")
      (node (ref "C79") (pin "2") (pinfunction "2_2") (pintype "passive"))
      (node (ref "IC1") (pin "J5") (pinfunction "VDD12O_VCO_SXT_J5") (pintype "power_in"))
      (node (ref "IC1") (pin "K6") (pinfunction "VDD12_VCO_SXT_K6") (pintype "power_in"))
    )
    (net (code "26") (name "Net-(IC1F-VDD12_DIG)") (class "Default")
      (node (ref "C57") (pin "1") (pinfunction "1_1") (pintype "passive"))
      (node (ref "IC1") (pin "C25") (pinfunction "VDD12_DIG_C25") (pintype "power_in"))
    )
    (net (code "27") (name "Net-(IC1F-VDD12_LNA_RFE)") (class "Default")
      (node (ref "C76") (pin "1") (pinfunction "1_1") (pintype "passive"))
      (node (ref "IC1") (pin "AG5") (pinfunction "VDD12_LNA_RFE_AG5") (pintype "power_in"))
    )
    (net (code "28") (name "Net-(IC1F-VDD12_RXBUF)") (class "Default")
      (node (ref "C72") (pin "1") (pinfunction "1_1") (pintype "passive"))
      (node (ref "IC1") (pin "AP26") (pinfunction "VDD12_RXBUF_AP26") (pintype "power_in"))
    )
    (net (code "29") (name "Net-(IC1F-VDD12_TIA_RFE)") (class "Default")
      (node (ref "C77") (pin "2") (pinfunction "2_2") (pintype "passive"))
      (node (ref "IC1") (pin "AD6") (pinfunction "VDD12_TIA_RFE_AD6") (pintype "power_in"))
    )
    (net (code "30") (name "Net-(IC1F-VDD12_TXBUF)") (class "Default")
      (node (ref "C80") (pin "1") (pinfunction "1_1") (pintype "passive"))
      (node (ref "IC1") (pin "G5") (pinfunction "VDD12_TXBUF_G5") (pintype "power_in"))
    )
    (net (code "31") (name "Net-(IC1F-VDD12_VCO_SXR)") (class "Default")
      (node (ref "C73") (pin "1") (pinfunction "1_1") (pintype "passive"))
      (node (ref "IC1") (pin "AN23") (pinfunction "VDD12_VCO_SXR_AN23") (pintype "power_in"))
    )
    (net (code "32") (name "Net-(IC1F-VDD14_LNA_RFE)") (class "Default")
      (node (ref "C83") (pin "1") (pinfunction "1_1") (pintype "passive"))
      (node (ref "IC1") (pin "AF6") (pinfunction "VDD14_LNA_RFE_AF6") (pintype "power_in"))
    )
    (net (code "33") (name "Net-(IC1F-VDD14_RBB)") (class "Default")
      (node (ref "C85") (pin "1") (pinfunction "1_1") (pintype "passive"))
      (node (ref "IC1") (pin "AD4") (pinfunction "VDD14_RBB_AD4") (pintype "power_in"))
    )
    (net (code "34") (name "Net-(IC1F-VDD14_TIA_RFE)") (class "Default")
      (node (ref "C84") (pin "1") (pinfunction "1_1") (pintype "passive"))
      (node (ref "IC1") (pin "AF2") (pinfunction "VDD14_TIA_RFE_AF2") (pintype "power_in"))
    )
    (net (code "35") (name "Net-(IC1F-VDD14_VCO_CGEN)") (class "Default")
      (node (ref "C82") (pin "1") (pinfunction "1_1") (pintype "passive"))
      (node (ref "IC1") (pin "C21") (pinfunction "VDD14_VCO_CGEN_C21") (pintype "power_in"))
    )
    (net (code "36") (name "Net-(IC1F-VDDO_DIV_SXT)") (class "Default")
      (node (ref "C81") (pin "1") (pinfunction "1_1") (pintype "passive"))
      (node (ref "IC1") (pin "K2") (pinfunction "VDDO_DIV_SXT_K2") (pintype "power_in"))
      (node (ref "IC1") (pin "L5") (pinfunction "VDD_DIV_SXT_L5") (pintype "power_in"))
    )
    (net (code "37") (name "Net-(IC1F-VDDO_TLOBUF_TRF)") (class "Default")
      (node (ref "C67") (pin "1") (pinfunction "1_1") (pintype "passive"))
      (node (ref "IC1") (pin "D6") (pinfunction "VDDO_TLOBUF_TRF_D6") (pintype "power_in"))
      (node (ref "IC1") (pin "F8") (pinfunction "VDD_TLOBUF_TRF_F8") (pintype "power_in"))
    )
    (net (code "38") (name "Net-(IC1F-VDD_AFE)") (class "Default")
      (node (ref "C71") (pin "1") (pinfunction "1_1") (pintype "passive"))
      (node (ref "IC1") (pin "AJ25") (pinfunction "VDD_AFE_AJ25") (pintype "power_in"))
    )
    (net (code "39") (name "Net-(IC1F-VDD_CP_CGEN)") (class "Default")
      (node (ref "C70") (pin "2") (pinfunction "2_2") (pintype "passive"))
      (node (ref "IC1") (pin "F20") (pinfunction "VDD_CP_CGEN_F20") (pintype "power_in"))
    )
    (net (code "40") (name "Net-(IC1F-VDD_CP_SXR)") (class "Default")
      (node (ref "C75") (pin "1") (pinfunction "1_1") (pintype "passive"))
      (node (ref "IC1") (pin "AL19") (pinfunction "VDD_CP_SXR_AL19") (pintype "power_in"))
    )
    (net (code "41") (name "Net-(IC1F-VDD_CP_SXT)") (class "Default")
      (node (ref "C78") (pin "1") (pinfunction "1_1") (pintype "passive"))
      (node (ref "IC1") (pin "J3") (pinfunction "VDD_CP_SXT_J3") (pintype "power_in"))
    )
    (net (code "42") (name "Net-(IC1F-VDD_DIV_CGEN)") (class "Default")
      (node (ref "C69") (pin "1") (pinfunction "1_1") (pintype "passive"))
      (node (ref "IC1") (pin "E19") (pinfunction "VDD_DIV_CGEN_E19") (pintype "power_in"))
    )
    (net (code "43") (name "Net-(IC1F-VDD_DIV_SXR)") (class "Default")
      (node (ref "C74") (pin "1") (pinfunction "1_1") (pintype "passive"))
      (node (ref "IC1") (pin "AM20") (pinfunction "VDD_DIV_SXR_AM20") (pintype "power_in"))
    )
    (net (code "44") (name "Net-(IC1F-VDD_MXLOBUF_RFE)") (class "Default")
      (node (ref "C86") (pin "1") (pinfunction "1_1") (pintype "passive"))
      (node (ref "IC1") (pin "AN17") (pinfunction "VDD_MXLOBUF_RFE_AN17") (pintype "power_in"))
    )
    (net (code "45") (name "Net-(IC1F-VDD_SPI_BUF)") (class "Default")
      (node (ref "C56") (pin "1") (pinfunction "1_1") (pintype "passive"))
      (node (ref "IC1") (pin "F24") (pinfunction "VDD_SPI_BUF_F24") (pintype "power_in"))
    )
    (net (code "46") (name "Net-(IC1F-VDD_TBB)") (class "Default")
      (node (ref "C66") (pin "1") (pinfunction "1_1") (pintype "passive"))
      (node (ref "IC1") (pin "P4") (pinfunction "VDD_TBB_P4") (pintype "power_in"))
    )
    (net (code "47") (name "Net-(IC1F-VDD_TPAD_TRF)") (class "Default")
      (node (ref "C68") (pin "1") (pinfunction "1_1") (pintype "passive"))
      (node (ref "IC1") (pin "B16") (pinfunction "VDD_TPAD_TRF_B16") (pintype "power_in"))
    )
    (net (code "48") (name "VCC1P8_LMS") (class "Default")
      (node (ref "FR1") (pin "2") (pinfunction "2_2") (pintype "passive"))
      (node (ref "FR2") (pin "1") (pinfunction "1_1") (pintype "passive"))
      (node (ref "FR3") (pin "1") (pinfunction "1_1") (pintype "passive"))
      (node (ref "FR4") (pin "2") (pinfunction "2_2") (pintype "passive"))
      (node (ref "FR5") (pin "2") (pinfunction "2_2") (pintype "passive"))
      (node (ref "FR6") (pin "2") (pinfunction "2_2") (pintype "passive"))
      (node (ref "FR7") (pin "2") (pinfunction "2_2") (pintype "passive"))
      (node (ref "FR8") (pin "2") (pinfunction "2_2") (pintype "passive"))
      (node (ref "R26") (pin "2") (pinfunction "2_2") (pintype "passive"))
      (node (ref "R32") (pin "2") (pinfunction "2_2") (pintype "passive"))
      (node (ref "R33") (pin "1") (pinfunction "1_1") (pintype "passive"))
    )
    (net (code "49") (name "VDIO_LMS") (class "Default")
      (node (ref "R27") (pin "1") (pinfunction "1_1") (pintype "passive"))
      (node (ref "R28") (pin "1") (pinfunction "1_1") (pintype "passive"))
      (node (ref "R29") (pin "1") (pinfunction "1_1") (pintype "passive"))
      (node (ref "R30") (pin "1") (pinfunction "1_1") (pintype "passive"))
      (node (ref "R31") (pin "1") (pinfunction "1_1") (pintype "passive"))
    )
  )
)
